# LISC_AFE.net
KiCad netlist of a schematic drawn in Altium Designer
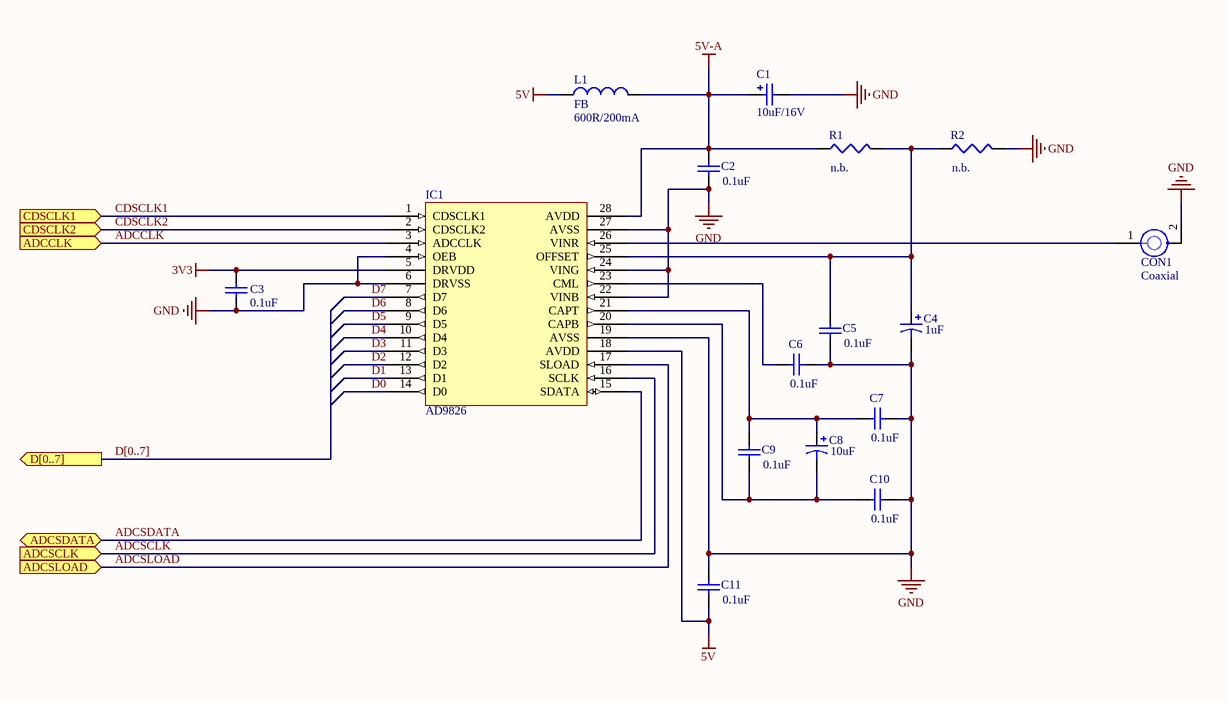
[diagram p0: LISC_AFE.SchDoc]

(export (version "E")
  (design (tool "Eeschema 10.0.6"))
  (components
    (comp (ref "C1")
      (value "10uF/16V")
      (footprint "C1210 Pol")
      (description "Polarized Capacitor (Surface Mount)")
      (fields (field (name "PUBLISHER") "Altium Limited"))
      (libsource (lib "Miscellaneous Devices_LT") (part "Cap EU SMD Pol"))
    )
    (comp (ref "C2")
      (value "0.1uF")
      (footprint "1608[0603]")
      (description "Capacitor (Semiconductor SIM Model)")
      (fields (field (name "PUBLISHER") "Altium Limited"))
      (libsource (lib "Miscellaneous Devices") (part "Cap Semi"))
    )
    (comp (ref "C3")
      (value "0.1uF")
      (footprint "1608[0603]")
      (description "Capacitor (Semiconductor SIM Model)")
      (fields (field (name "Comment") "Cap Semi") (field (name "PUBLISHER") "Altium Limited"))
      (libsource (lib "Miscellaneous Devices") (part "Cap Semi"))
    )
    (comp (ref "C4")
      (value "1uF")
      (footprint "C0805")
      (description "Polarized Capacitor (Surface Mount)")
      (fields (field (name "PUBLISHER") "Altium Limited"))
      (libsource (lib "Miscellaneous Devices") (part "Cap Pol3"))
    )
    (comp (ref "C5")
      (value "0.1uF")
      (footprint "1608[0603]")
      (description "Capacitor (Semiconductor SIM Model)")
      (fields (field (name "PUBLISHER") "Altium Limited"))
      (libsource (lib "Miscellaneous Devices") (part "Cap Semi"))
    )
    (comp (ref "C6")
      (value "0.1uF")
      (footprint "1608[0603]")
      (description "Capacitor (Semiconductor SIM Model)")
      (fields (field (name "PUBLISHER") "Altium Limited"))
      (libsource (lib "Miscellaneous Devices") (part "Cap Semi"))
    )
    (comp (ref "C7")
      (value "0.1uF")
      (footprint "1608[0603]")
      (description "Capacitor (Semiconductor SIM Model)")
      (fields (field (name "PUBLISHER") "Altium Limited"))
      (libsource (lib "Miscellaneous Devices") (part "Cap Semi"))
    )
    (comp (ref "C8")
      (value "10uF")
      (footprint "C0805")
      (description "Polarized Capacitor (Surface Mount)")
      (fields (field (name "PUBLISHER") "Altium Limited"))
      (libsource (lib "Miscellaneous Devices") (part "Cap Pol3"))
    )
    (comp (ref "C9")
      (value "0.1uF")
      (footprint "1608[0603]")
      (description "Capacitor (Semiconductor SIM Model)")
      (fields (field (name "PUBLISHER") "Altium Limited"))
      (libsource (lib "Miscellaneous Devices") (part "Cap Semi"))
    )
    (comp (ref "C10")
      (value "0.1uF")
      (footprint "1608[0603]")
      (description "Capacitor (Semiconductor SIM Model)")
      (fields (field (name "PUBLISHER") "Altium Limited"))
      (libsource (lib "Miscellaneous Devices") (part "Cap Semi"))
    )
    (comp (ref "C11")
      (value "0.1uF")
      (footprint "1608[0603]")
      (description "Capacitor (Semiconductor SIM Model)")
      (fields (field (name "PUBLISHER") "Altium Limited"))
      (libsource (lib "Miscellaneous Devices") (part "Cap Semi"))
    )
    (comp (ref "CON1")
      (value "Coaxial")
      (footprint "U.FL-R-SMT")
      (libsource (lib "RF-Coaxial") (part "Coaxial"))
    )
    (comp (ref "IC1")
      (value "AD9826")
      (footprint "SOP65P780-28AM")
      (libsource (lib "AD9826") (part "AD9826"))
    )
    (comp (ref "L1")
      (value "FB")
      (footprint "INDC1608L")
      (description "Inductor")
      (fields (field (name "ALTIUM_VALUE") "600R/200mA") (field (name "PUBLISHER") "Altium Limited"))
      (libsource (lib "Miscellaneous Devices_LT") (part "Inductor"))
    )
    (comp (ref "R1")
      (value "n.b.")
      (footprint "J1-0603")
      (description "Resistor")
      (fields (field (name "PUBLISHER") "Altium Limited"))
      (libsource (lib "Miscellaneous Devices") (part "Res3"))
    )
    (comp (ref "R2")
      (value "n.b.")
      (footprint "J1-0603")
      (description "Resistor")
      (fields (field (name "PUBLISHER") "Altium Limited"))
      (libsource (lib "Miscellaneous Devices") (part "Res3"))
    )
  )
  (nets
    (net (code "1") (name "/ADCCLK") (class "Default")
      (node (ref "IC1") (pin "3") (pinfunction "ADCCLK_3") (pintype "input"))
    )
    (net (code "2") (name "/ADCSCLK") (class "Default")
      (node (ref "IC1") (pin "16") (pinfunction "SCLK_16") (pintype "input"))
    )
    (net (code "3") (name "/ADCSDATA") (class "Default")
      (node (ref "IC1") (pin "15") (pinfunction "SDATA_15") (pintype "bidirectional"))
    )
    (net (code "4") (name "/ADCSLOAD") (class "Default")
      (node (ref "IC1") (pin "17") (pinfunction "SLOAD_17") (pintype "input"))
    )
    (net (code "5") (name "/CDSCLK1") (class "Default")
      (node (ref "IC1") (pin "1") (pinfunction "CDSCLK1_1") (pintype "input"))
    )
    (net (code "6") (name "/CDSCLK2") (class "Default")
      (node (ref "IC1") (pin "2") (pinfunction "CDSCLK2_2") (pintype "input"))
    )
    (net (code "7") (name "/D0") (class "Default")
      (node (ref "IC1") (pin "14") (pinfunction "D0_14") (pintype "output"))
    )
    (net (code "8") (name "/D1") (class "Default")
      (node (ref "IC1") (pin "13") (pinfunction "D1_13") (pintype "output"))
    )
    (net (code "9") (name "/D2") (class "Default")
      (node (ref "IC1") (pin "12") (pinfunction "D2_12") (pintype "output"))
    )
    (net (code "10") (name "/D3") (class "Default")
      (node (ref "IC1") (pin "11") (pinfunction "D3_11") (pintype "output"))
    )
    (net (code "11") (name "/D4") (class "Default")
      (node (ref "IC1") (pin "10") (pinfunction "D4_10") (pintype "output"))
    )
    (net (code "12") (name "/D5") (class "Default")
      (node (ref "IC1") (pin "9") (pinfunction "D5_9") (pintype "output"))
    )
    (net (code "13") (name "/D6") (class "Default")
      (node (ref "IC1") (pin "8") (pinfunction "D6_8") (pintype "output"))
    )
    (net (code "14") (name "/D7") (class "Default")
      (node (ref "IC1") (pin "7") (pinfunction "D7_7") (pintype "output"))
    )
    (net (code "16") (name "3V3") (class "Default")
      (node (ref "C3") (pin "1") (pinfunction "1_1") (pintype "passive"))
      (node (ref "IC1") (pin "5") (pinfunction "DRVDD_5") (pintype "power_in"))
    )
    (net (code "17") (name "5V") (class "Default")
      (node (ref "C11") (pin "1") (pinfunction "1_1") (pintype "passive"))
      (node (ref "IC1") (pin "18") (pinfunction "AVDD_18") (pintype "power_in"))
      (node (ref "L1") (pin "1") (pinfunction "1_1") (pintype "passive"))
    )
    (net (code "18") (name "5V-A") (class "Default")
      (node (ref "C1") (pin "1") (pinfunction "1_1") (pintype "passive"))
      (node (ref "C2") (pin "2") (pinfunction "2_2") (pintype "passive"))
      (node (ref "IC1") (pin "28") (pinfunction "AVDD_28") (pintype "power_in"))
      (node (ref "L1") (pin "2") (pinfunction "2_2") (pintype "passive"))
      (node (ref "R1") (pin "1") (pinfunction "1_1") (pintype "passive"))
    )
    (net (code "19") (name "GND") (class "Default")
      (node (ref "C1") (pin "2") (pinfunction "2_2") (pintype "passive"))
      (node (ref "C10") (pin "1") (pinfunction "1_1") (pintype "passive"))
      (node (ref "C11") (pin "2") (pinfunction "2_2") (pintype "passive"))
      (node (ref "C2") (pin "1") (pinfunction "1_1") (pintype "passive"))
      (node (ref "C3") (pin "2") (pinfunction "2_2") (pintype "passive"))
      (node (ref "C4") (pin "2") (pinfunction "2_2") (pintype "passive"))
      (node (ref "C5") (pin "1") (pinfunction "1_1") (pintype "passive"))
      (node (ref "C6") (pin "1") (pinfunction "1_1") (pintype "passive"))
      (node (ref "C7") (pin "1") (pinfunction "1_1") (pintype "passive"))
      (node (ref "CON1") (pin "2") (pinfunction "2_2") (pintype "passive"))
      (node (ref "IC1") (pin "19") (pinfunction "AVSS_19") (pintype "power_in"))
      (node (ref "IC1") (pin "22") (pinfunction "VINB_22") (pintype "input"))
      (node (ref "IC1") (pin "24") (pinfunction "VING_24") (pintype "input"))
      (node (ref "IC1") (pin "27") (pinfunction "AVSS_27") (pintype "power_in"))
      (node (ref "IC1") (pin "4") (pinfunction "OEB_4") (pintype "input"))
      (node (ref "IC1") (pin "6") (pinfunction "DRVSS_6") (pintype "power_in"))
      (node (ref "R2") (pin "2") (pinfunction "2_2") (pintype "passive"))
    )
    (net (code "20") (name "Net-(IC1-CAPB)") (class "Default")
      (node (ref "C10") (pin "2") (pinfunction "2_2") (pintype "passive"))
      (node (ref "C8") (pin "2") (pinfunction "2_2") (pintype "passive"))
      (node (ref "C9") (pin "1") (pinfunction "1_1") (pintype "passive"))
      (node (ref "IC1") (pin "20") (pinfunction "CAPB_20") (pintype "output"))
    )
    (net (code "21") (name "Net-(IC1-CAPT)") (class "Default")
      (node (ref "C7") (pin "2") (pinfunction "2_2") (pintype "passive"))
      (node (ref "C8") (pin "1") (pinfunction "1_1") (pintype "passive"))
      (node (ref "C9") (pin "2") (pinfunction "2_2") (pintype "passive"))
      (node (ref "IC1") (pin "21") (pinfunction "CAPT_21") (pintype "output"))
    )
    (net (code "22") (name "Net-(IC1-CML)") (class "Default")
      (node (ref "C6") (pin "2") (pinfunction "2_2") (pintype "passive"))
      (node (ref "IC1") (pin "23") (pinfunction "CML_23") (pintype "output"))
    )
    (net (code "23") (name "Net-(IC1-OFFSET)") (class "Default")
      (node (ref "C4") (pin "1") (pinfunction "1_1") (pintype "passive"))
      (node (ref "C5") (pin "2") (pinfunction "2_2") (pintype "passive"))
      (node (ref "IC1") (pin "25") (pinfunction "OFFSET_25") (pintype "output"))
      (node (ref "R1") (pin "2") (pinfunction "2_2") (pintype "passive"))
      (node (ref "R2") (pin "1") (pinfunction "1_1") (pintype "passive"))
    )
    (net (code "24") (name "Net-(IC1-VINR)") (class "Default")
      (node (ref "CON1") (pin "1") (pinfunction "1_1") (pintype "passive"))
      (node (ref "IC1") (pin "26") (pinfunction "VINR_26") (pintype "input"))
    )
  )
)
